# nRF24L01.net
KiCad netlist of a schematic drawn in Altium Designer
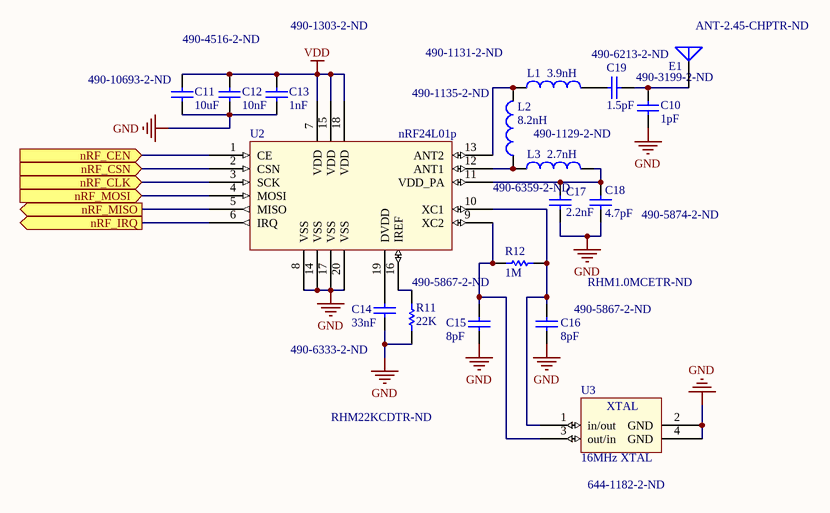
[diagram p0: nRF24L01.SchDoc]

(export (version "E")
  (design (tool "Eeschema 10.0.6"))
  (components
    (comp (ref "C10")
      (value "1pF")
      (footprint "0402")
      (description "Capacitor (Semiconductor SIM Model)")
      (fields
        (field (name "SUPPLIER PART NUMBER 1") "490-3199-2-ND")
        (field (name "PUBLISHER") "Altium Limited")
      )
      (libsource (lib "Miscellaneous Devices") (part "Cap Semi"))
    )
    (comp (ref "C11")
      (value "10uF")
      (footprint "0402")
      (description "Capacitor (Semiconductor SIM Model)")
      (fields
        (field (name "SUPPLIER PART NUMBER 1") "490-10693-2-ND")
        (field (name "PUBLISHER") "Altium Limited")
      )
      (libsource (lib "Miscellaneous Devices") (part "Cap Semi"))
    )
    (comp (ref "C12")
      (value "10nF")
      (footprint "0402")
      (description "Capacitor (Semiconductor SIM Model)")
      (fields
        (field (name "SUPPLIER PART NUMBER 1") "490-4516-2-ND")
        (field (name "PUBLISHER") "Altium Limited")
      )
      (libsource (lib "Miscellaneous Devices") (part "Cap Semi"))
    )
    (comp (ref "C13")
      (value "1nF")
      (footprint "0402")
      (description "Capacitor (Semiconductor SIM Model)")
      (fields
        (field (name "SUPPLIER PART NUMBER 1") "490-1303-2-ND")
        (field (name "PUBLISHER") "Altium Limited")
      )
      (libsource (lib "Miscellaneous Devices") (part "Cap Semi"))
    )
    (comp (ref "C14")
      (value "33nF")
      (footprint "0402")
      (description "Capacitor (Semiconductor SIM Model)")
      (fields
        (field (name "SUPPLIER PART NUMBER 1") "490-6333-2-ND")
        (field (name "PUBLISHER") "Altium Limited")
      )
      (libsource (lib "Miscellaneous Devices") (part "Cap Semi"))
    )
    (comp (ref "C15")
      (value "8pF")
      (footprint "0402")
      (description "Capacitor (Semiconductor SIM Model)")
      (fields
        (field (name "SUPPLIER PART NUMBER 1") "490-5867-2-ND")
        (field (name "PUBLISHER") "Altium Limited")
      )
      (libsource (lib "Miscellaneous Devices") (part "Cap Semi"))
    )
    (comp (ref "C16")
      (value "8pF")
      (footprint "0402")
      (description "Capacitor (Semiconductor SIM Model)")
      (fields
        (field (name "SUPPLIER PART NUMBER 1") "490-5867-2-ND")
        (field (name "PUBLISHER") "Altium Limited")
      )
      (libsource (lib "Miscellaneous Devices") (part "Cap Semi"))
    )
    (comp (ref "C17")
      (value "2.2nF")
      (footprint "0402")
      (description "Capacitor (Semiconductor SIM Model)")
      (fields
        (field (name "SUPPLIER PART NUMBER 1") "490-6359-2-ND")
        (field (name "PUBLISHER") "Altium Limited")
      )
      (libsource (lib "Miscellaneous Devices") (part "Cap Semi"))
    )
    (comp (ref "C18")
      (value "4.7pF")
      (footprint "0402")
      (description "Capacitor (Semiconductor SIM Model)")
      (fields
        (field (name "SUPPLIER PART NUMBER 1") "490-5874-2-ND")
        (field (name "PUBLISHER") "Altium Limited")
      )
      (libsource (lib "Miscellaneous Devices") (part "Cap Semi"))
    )
    (comp (ref "C19")
      (value "1.5pF")
      (footprint "0402")
      (description "Capacitor (Semiconductor SIM Model)")
      (fields
        (field (name "SUPPLIER PART NUMBER 1") "490-6213-2-ND")
        (field (name "PUBLISHER") "Altium Limited")
      )
      (libsource (lib "Miscellaneous Devices") (part "Cap Semi"))
    )
    (comp (ref "E1")
      (value "~")
      (footprint "ANT-2.45-CHP-B")
      (description "Generic Antenna")
      (fields
        (field (name "SUPPLIER PART NUMBER 1") "ANT-2.45-CHPTR-ND")
        (field (name "PUBLISHER") "Altium Limited")
      )
      (libsource (lib "Miscellaneous Devices") (part "Antenna"))
    )
    (comp (ref "L1")
      (value "3.9nH")
      (footprint "0402")
      (description "Inductor")
      (fields
        (field (name "SUPPLIER PART NUMBER 1") "490-1131-2-ND")
        (field (name "PUBLISHER") "Altium Limited")
      )
      (libsource (lib "Miscellaneous Devices") (part "Inductor"))
    )
    (comp (ref "L2")
      (value "8.2nH")
      (footprint "0402")
      (description "Inductor")
      (fields
        (field (name "SUPPLIER PART NUMBER 1") "490-1135-2-ND")
        (field (name "PUBLISHER") "Altium Limited")
      )
      (libsource (lib "Miscellaneous Devices") (part "Inductor"))
    )
    (comp (ref "L3")
      (value "2.7nH")
      (footprint "0402")
      (description "Inductor")
      (fields
        (field (name "SUPPLIER PART NUMBER 1") "490-1129-2-ND")
        (field (name "PUBLISHER") "Altium Limited")
      )
      (libsource (lib "Miscellaneous Devices") (part "Inductor"))
    )
    (comp (ref "R11")
      (value "22K")
      (footprint "0402")
      (description "Semiconductor Resistor")
      (fields
        (field (name "SUPPLIER PART NUMBER 1") "RHM22KCDTR-ND")
        (field (name "PUBLISHER") "Altium Limited")
      )
      (libsource (lib "Miscellaneous Devices") (part "Res Semi"))
    )
    (comp (ref "R12")
      (value "1M")
      (footprint "0402")
      (description "Semiconductor Resistor")
      (fields
        (field (name "SUPPLIER PART NUMBER 1") "RHM1.0MCETR-ND")
        (field (name "PUBLISHER") "Altium Limited")
      )
      (libsource (lib "Miscellaneous Devices") (part "Res Semi"))
    )
    (comp (ref "U2")
      (value "nRF24L01p")
      (footprint "Component_nRF")
      (libsource (lib "nRF24L01") (part "Component_nRF"))
    )
    (comp (ref "U3")
      (value "16MHz XTAL")
      (footprint "8Y-16.000MAAV-T")
      (description "SMD 16 MHz XTAL")
      (fields (field (name "SUPPLIER PART NUMBER 1") "644-1182-2-ND"))
      (libsource (lib "headstage_parts") (part "8Y-16.000MAAV-T"))
    )
  )
  (nets
    (net (code "1") (name "/nRF_CEN") (class "Default")
      (node (ref "U2") (pin "1") (pinfunction "CE_1") (pintype "input"))
    )
    (net (code "2") (name "/nRF_CLK") (class "Default")
      (node (ref "U2") (pin "3") (pinfunction "SCK_3") (pintype "input"))
    )
    (net (code "3") (name "/nRF_CSN") (class "Default")
      (node (ref "U2") (pin "2") (pinfunction "CSN_2") (pintype "input"))
    )
    (net (code "4") (name "/nRF_IRQ") (class "Default")
      (node (ref "U2") (pin "6") (pinfunction "IRQ_6") (pintype "output"))
    )
    (net (code "5") (name "/nRF_MISO") (class "Default")
      (node (ref "U2") (pin "5") (pinfunction "MISO_5") (pintype "output"))
    )
    (net (code "6") (name "/nRF_MOSI") (class "Default")
      (node (ref "U2") (pin "4") (pinfunction "MOSI_4") (pintype "input"))
    )
    (net (code "7") (name "GND") (class "Default")
      (node (ref "C10") (pin "2") (pinfunction "2_2") (pintype "passive"))
      (node (ref "C11") (pin "1") (pinfunction "1_1") (pintype "passive"))
      (node (ref "C12") (pin "1") (pinfunction "1_1") (pintype "passive"))
      (node (ref "C13") (pin "1") (pinfunction "1_1") (pintype "passive"))
      (node (ref "C14") (pin "1") (pinfunction "1_1") (pintype "passive"))
      (node (ref "C15") (pin "1") (pinfunction "1_1") (pintype "passive"))
      (node (ref "C16") (pin "1") (pinfunction "1_1") (pintype "passive"))
      (node (ref "C17") (pin "1") (pinfunction "1_1") (pintype "passive"))
      (node (ref "C18") (pin "1") (pinfunction "1_1") (pintype "passive"))
      (node (ref "R11") (pin "1") (pinfunction "1_1") (pintype "passive"))
      (node (ref "U2") (pin "14") (pinfunction "VSS_14") (pintype "power_in"))
      (node (ref "U2") (pin "17") (pinfunction "VSS_17") (pintype "power_in"))
      (node (ref "U2") (pin "20") (pinfunction "VSS_20") (pintype "power_in"))
      (node (ref "U2") (pin "8") (pinfunction "VSS_8") (pintype "power_in"))
      (node (ref "U3") (pin "2") (pinfunction "GND_2") (pintype "power_in"))
      (node (ref "U3") (pin "4") (pinfunction "GND_4") (pintype "power_in"))
    )
    (net (code "8") (name "Net-(C19-Pad2)") (class "Default")
      (node (ref "C19") (pin "2") (pinfunction "2_2") (pintype "passive"))
      (node (ref "L1") (pin "2") (pinfunction "2_2") (pintype "passive"))
    )
    (net (code "9") (name "Net-(E1-A)") (class "Default")
      (node (ref "C10") (pin "1") (pinfunction "1_1") (pintype "passive"))
      (node (ref "C19") (pin "1") (pinfunction "1_1") (pintype "passive"))
      (node (ref "E1") (pin "1") (pinfunction "A_1") (pintype "passive"))
    )
    (net (code "10") (name "Net-(U2-ANT1)") (class "Default")
      (node (ref "L2") (pin "1") (pinfunction "1_1") (pintype "passive"))
      (node (ref "L3") (pin "1") (pinfunction "1_1") (pintype "passive"))
      (node (ref "U2") (pin "12") (pinfunction "ANT1_12") (pintype "bidirectional"))
    )
    (net (code "11") (name "Net-(U2-ANT2)") (class "Default")
      (node (ref "L1") (pin "1") (pinfunction "1_1") (pintype "passive"))
      (node (ref "L2") (pin "2") (pinfunction "2_2") (pintype "passive"))
      (node (ref "U2") (pin "13") (pinfunction "ANT2_13") (pintype "bidirectional"))
    )
    (net (code "12") (name "Net-(U2-DVDD)") (class "Default")
      (node (ref "C14") (pin "2") (pinfunction "2_2") (pintype "passive"))
      (node (ref "U2") (pin "19") (pinfunction "DVDD_19") (pintype "power_in"))
    )
    (net (code "13") (name "Net-(U2-IREF)") (class "Default")
      (node (ref "R11") (pin "2") (pinfunction "2_2") (pintype "passive"))
      (node (ref "U2") (pin "16") (pinfunction "IREF_16") (pintype "bidirectional"))
    )
    (net (code "14") (name "Net-(U2-VDD_PA)") (class "Default")
      (node (ref "C17") (pin "2") (pinfunction "2_2") (pintype "passive"))
      (node (ref "C18") (pin "2") (pinfunction "2_2") (pintype "passive"))
      (node (ref "L3") (pin "2") (pinfunction "2_2") (pintype "passive"))
      (node (ref "U2") (pin "11") (pinfunction "VDD_PA_11") (pintype "bidirectional"))
    )
    (net (code "15") (name "Net-(U2-XC1)") (class "Default")
      (node (ref "C16") (pin "2") (pinfunction "2_2") (pintype "passive"))
      (node (ref "R12") (pin "1") (pinfunction "1_1") (pintype "passive"))
      (node (ref "U2") (pin "10") (pinfunction "XC1_10") (pintype "bidirectional"))
      (node (ref "U3") (pin "1") (pinfunction "in/out_1") (pintype "bidirectional"))
    )
    (net (code "16") (name "Net-(U2-XC2)") (class "Default")
      (node (ref "C15") (pin "2") (pinfunction "2_2") (pintype "passive"))
      (node (ref "R12") (pin "2") (pinfunction "2_2") (pintype "passive"))
      (node (ref "U2") (pin "9") (pinfunction "XC2_9") (pintype "bidirectional"))
      (node (ref "U3") (pin "3") (pinfunction "out/in_3") (pintype "bidirectional"))
    )
    (net (code "17") (name "VDD") (class "Default")
      (node (ref "C11") (pin "2") (pinfunction "2_2") (pintype "passive"))
      (node (ref "C12") (pin "2") (pinfunction "2_2") (pintype "passive"))
      (node (ref "C13") (pin "2") (pinfunction "2_2") (pintype "passive"))
      (node (ref "U2") (pin "15") (pinfunction "VDD_15") (pintype "power_in"))
      (node (ref "U2") (pin "18") (pinfunction "VDD_18") (pintype "power_in"))
      (node (ref "U2") (pin "7") (pinfunction "VDD_7") (pintype "power_in"))
    )
  )
)
